# lights_switch_one.net
KiCad netlist of a schematic drawn in EAGLE
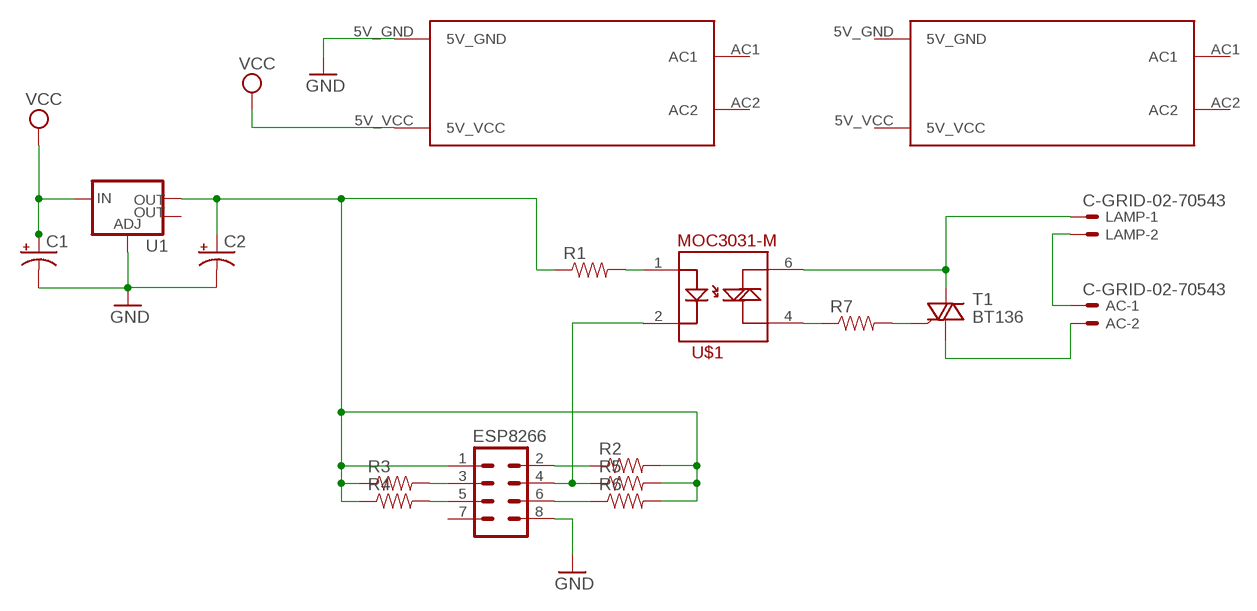
[diagram p0: schematic, sheet 1]

(export (version "E")
  (design (tool "Eeschema 10.0.6"))
  (components
    (comp (ref "AC")
      (value "C-GRID-02-70543")
      (footprint "eagle-import:70543-02")
      (libsource (lib "eagle-import") (part "C-GRID-02-70543"))
    )
    (comp (ref "C1")
      (value "CAP_POL1206")
      (footprint "eagle-import:EIA3216")
      (libsource (lib "eagle-import") (part "CAP_POL1206"))
    )
    (comp (ref "C2")
      (value "CAP_POL1206")
      (footprint "eagle-import:EIA3216")
      (libsource (lib "eagle-import") (part "CAP_POL1206"))
    )
    (comp (ref "ESP8266")
      (value "M04X2")
      (footprint "eagle-import:2X4")
      (libsource (lib "eagle-import") (part "M04X2"))
    )
    (comp (ref "LAMP")
      (value "C-GRID-02-70543")
      (footprint "eagle-import:70543-02")
      (libsource (lib "eagle-import") (part "C-GRID-02-70543"))
    )
    (comp (ref "R1")
      (value "RESISTOR1206")
      (footprint "eagle-import:1206")
      (libsource (lib "eagle-import") (part "RESISTOR1206"))
    )
    (comp (ref "R2")
      (value "RESISTOR1206")
      (footprint "eagle-import:1206")
      (libsource (lib "eagle-import") (part "RESISTOR1206"))
    )
    (comp (ref "R3")
      (value "RESISTOR1206")
      (footprint "eagle-import:1206")
      (libsource (lib "eagle-import") (part "RESISTOR1206"))
    )
    (comp (ref "R4")
      (value "RESISTOR1206")
      (footprint "eagle-import:1206")
      (libsource (lib "eagle-import") (part "RESISTOR1206"))
    )
    (comp (ref "R5")
      (value "RESISTOR1206")
      (footprint "eagle-import:1206")
      (libsource (lib "eagle-import") (part "RESISTOR1206"))
    )
    (comp (ref "R6")
      (value "RESISTOR1206")
      (footprint "eagle-import:1206")
      (libsource (lib "eagle-import") (part "RESISTOR1206"))
    )
    (comp (ref "R7")
      (value "RESISTOR1206")
      (footprint "eagle-import:1206")
      (libsource (lib "eagle-import") (part "RESISTOR1206"))
    )
    (comp (ref "T1")
      (value "BT136")
      (footprint "eagle-import:TO220AB")
      (libsource (lib "eagle-import") (part "BT136"))
    )
    (comp (ref "U$1")
      (value "MOC3031-M")
      (footprint "eagle-import:DIL06")
      (libsource (lib "eagle-import") (part "MOC3031-M"))
    )
    (comp (ref "U$2")
      (value "HI-LINK5V-ACDC")
      (footprint "eagle-import:AC5V")
      (libsource (lib "eagle-import") (part "HI-LINK5V-ACDC"))
    )
    (comp (ref "U$3")
      (value "HI-LINK5V-ACDC")
      (footprint "eagle-import:AC5V")
      (libsource (lib "eagle-import") (part "HI-LINK5V-ACDC"))
    )
    (comp (ref "U1")
      (value "V_REG_LM1117SOT223")
      (footprint "eagle-import:SOT223")
      (libsource (lib "eagle-import") (part "V_REG_LM1117SOT223"))
    )
  )
  (nets
    (net (code "1") (name "GND") (class "Default")
      (node (ref "C1") (pin "C") (pinfunction "-_C") (pintype "passive"))
      (node (ref "C2") (pin "C") (pinfunction "-_C") (pintype "passive"))
      (node (ref "ESP8266") (pin "8") (pinfunction "8_8") (pintype "passive"))
      (node (ref "U$2") (pin "5V_GND") (pinfunction "5V_GND_5V_GND") (pintype "bidirectional"))
      (node (ref "U1") (pin "1") (pinfunction "ADJ_1") (pintype "input"))
    )
    (net (code "2") (name "Net-(ACA-S)") (class "Default")
      (node (ref "AC") (pin "1") (pinfunction "S_1") (pintype "passive"))
      (node (ref "LAMP") (pin "2") (pinfunction "S_2") (pintype "passive"))
    )
    (net (code "3") (name "Net-(ACB-S)") (class "Default")
      (node (ref "AC") (pin "2") (pinfunction "S_2") (pintype "passive"))
      (node (ref "T1") (pin "1") (pinfunction "A1_1") (pintype "passive"))
    )
    (net (code "4") (name "Net-(C2-+)") (class "Default")
      (node (ref "C2") (pin "A") (pinfunction "+_A") (pintype "passive"))
      (node (ref "ESP8266") (pin "1") (pinfunction "1_1") (pintype "passive"))
      (node (ref "R1") (pin "1") (pinfunction "1_1") (pintype "passive"))
      (node (ref "R2") (pin "2") (pinfunction "2_2") (pintype "passive"))
      (node (ref "R3") (pin "1") (pinfunction "1_1") (pintype "passive"))
      (node (ref "R4") (pin "1") (pinfunction "1_1") (pintype "passive"))
      (node (ref "R5") (pin "2") (pinfunction "2_2") (pintype "passive"))
      (node (ref "R6") (pin "2") (pinfunction "2_2") (pintype "passive"))
      (node (ref "U1") (pin "2") (pinfunction "OUT_2") (pintype "output"))
    )
    (net (code "5") (name "Net-(ESP8266-Pad2)") (class "Default")
      (node (ref "ESP8266") (pin "2") (pinfunction "2_2") (pintype "passive"))
      (node (ref "R2") (pin "1") (pinfunction "1_1") (pintype "passive"))
    )
    (net (code "6") (name "Net-(ESP8266-Pad3)") (class "Default")
      (node (ref "ESP8266") (pin "3") (pinfunction "3_3") (pintype "passive"))
      (node (ref "R3") (pin "2") (pinfunction "2_2") (pintype "passive"))
    )
    (net (code "7") (name "Net-(ESP8266-Pad4)") (class "Default")
      (node (ref "ESP8266") (pin "4") (pinfunction "4_4") (pintype "passive"))
      (node (ref "R5") (pin "1") (pinfunction "1_1") (pintype "passive"))
      (node (ref "U$1") (pin "2") (pinfunction "2_2") (pintype "bidirectional"))
    )
    (net (code "8") (name "Net-(ESP8266-Pad5)") (class "Default")
      (node (ref "ESP8266") (pin "5") (pinfunction "5_5") (pintype "passive"))
      (node (ref "R4") (pin "2") (pinfunction "2_2") (pintype "passive"))
    )
    (net (code "9") (name "Net-(ESP8266-Pad6)") (class "Default")
      (node (ref "ESP8266") (pin "6") (pinfunction "6_6") (pintype "passive"))
      (node (ref "R6") (pin "1") (pinfunction "1_1") (pintype "passive"))
    )
    (net (code "10") (name "Net-(LAMPA-S)") (class "Default")
      (node (ref "LAMP") (pin "1") (pinfunction "S_1") (pintype "passive"))
      (node (ref "T1") (pin "2") (pinfunction "A2_2") (pintype "passive"))
      (node (ref "U$1") (pin "6") (pinfunction "6_6") (pintype "bidirectional"))
    )
    (net (code "11") (name "Net-(R1-Pad2)") (class "Default")
      (node (ref "R1") (pin "2") (pinfunction "2_2") (pintype "passive"))
      (node (ref "U$1") (pin "1") (pinfunction "1_1") (pintype "bidirectional"))
    )
    (net (code "12") (name "Net-(R7-Pad1)") (class "Default")
      (node (ref "R7") (pin "1") (pinfunction "1_1") (pintype "passive"))
      (node (ref "U$1") (pin "4") (pinfunction "4_4") (pintype "bidirectional"))
    )
    (net (code "13") (name "Net-(T1-G)") (class "Default")
      (node (ref "R7") (pin "2") (pinfunction "2_2") (pintype "passive"))
      (node (ref "T1") (pin "3") (pinfunction "G_3") (pintype "passive"))
    )
    (net (code "14") (name "VCC") (class "Default")
      (node (ref "C1") (pin "A") (pinfunction "+_A") (pintype "passive"))
      (node (ref "U$2") (pin "5V_VCC") (pinfunction "5V_VCC_5V_VCC") (pintype "bidirectional"))
      (node (ref "U1") (pin "3") (pinfunction "IN_3") (pintype "input"))
    )
    (net (code "15") (name "unconnected-(ESP8266-Pad7)") (class "Default")
      (node (ref "ESP8266") (pin "7") (pinfunction "7_7") (pintype "passive"))
    )
    (net (code "16") (name "unconnected-(U$2-PadAC1)") (class "Default")
      (node (ref "U$2") (pin "AC1") (pinfunction "AC1_AC1") (pintype "bidirectional"))
    )
    (net (code "17") (name "unconnected-(U$2-PadAC2)") (class "Default")
      (node (ref "U$2") (pin "AC2") (pinfunction "AC2_AC2") (pintype "bidirectional"))
    )
    (net (code "18") (name "unconnected-(U$3-Pad5V_GND)") (class "Default")
      (node (ref "U$3") (pin "5V_GND") (pinfunction "5V_GND_5V_GND") (pintype "bidirectional"))
    )
    (net (code "19") (name "unconnected-(U$3-Pad5V_VCC)") (class "Default")
      (node (ref "U$3") (pin "5V_VCC") (pinfunction "5V_VCC_5V_VCC") (pintype "bidirectional"))
    )
    (net (code "20") (name "unconnected-(U$3-PadAC1)") (class "Default")
      (node (ref "U$3") (pin "AC1") (pinfunction "AC1_AC1") (pintype "bidirectional"))
    )
    (net (code "21") (name "unconnected-(U$3-PadAC2)") (class "Default")
      (node (ref "U$3") (pin "AC2") (pinfunction "AC2_AC2") (pintype "bidirectional"))
    )
    (net (code "22") (name "unconnected-(U1-OUT-Pad4)") (class "Default")
      (node (ref "U1") (pin "4") (pinfunction "OUT_4") (pintype "output"))
    )
  )
)
